# OR_Power_Switch.net
KiCad netlist of a schematic drawn in Altium Designer
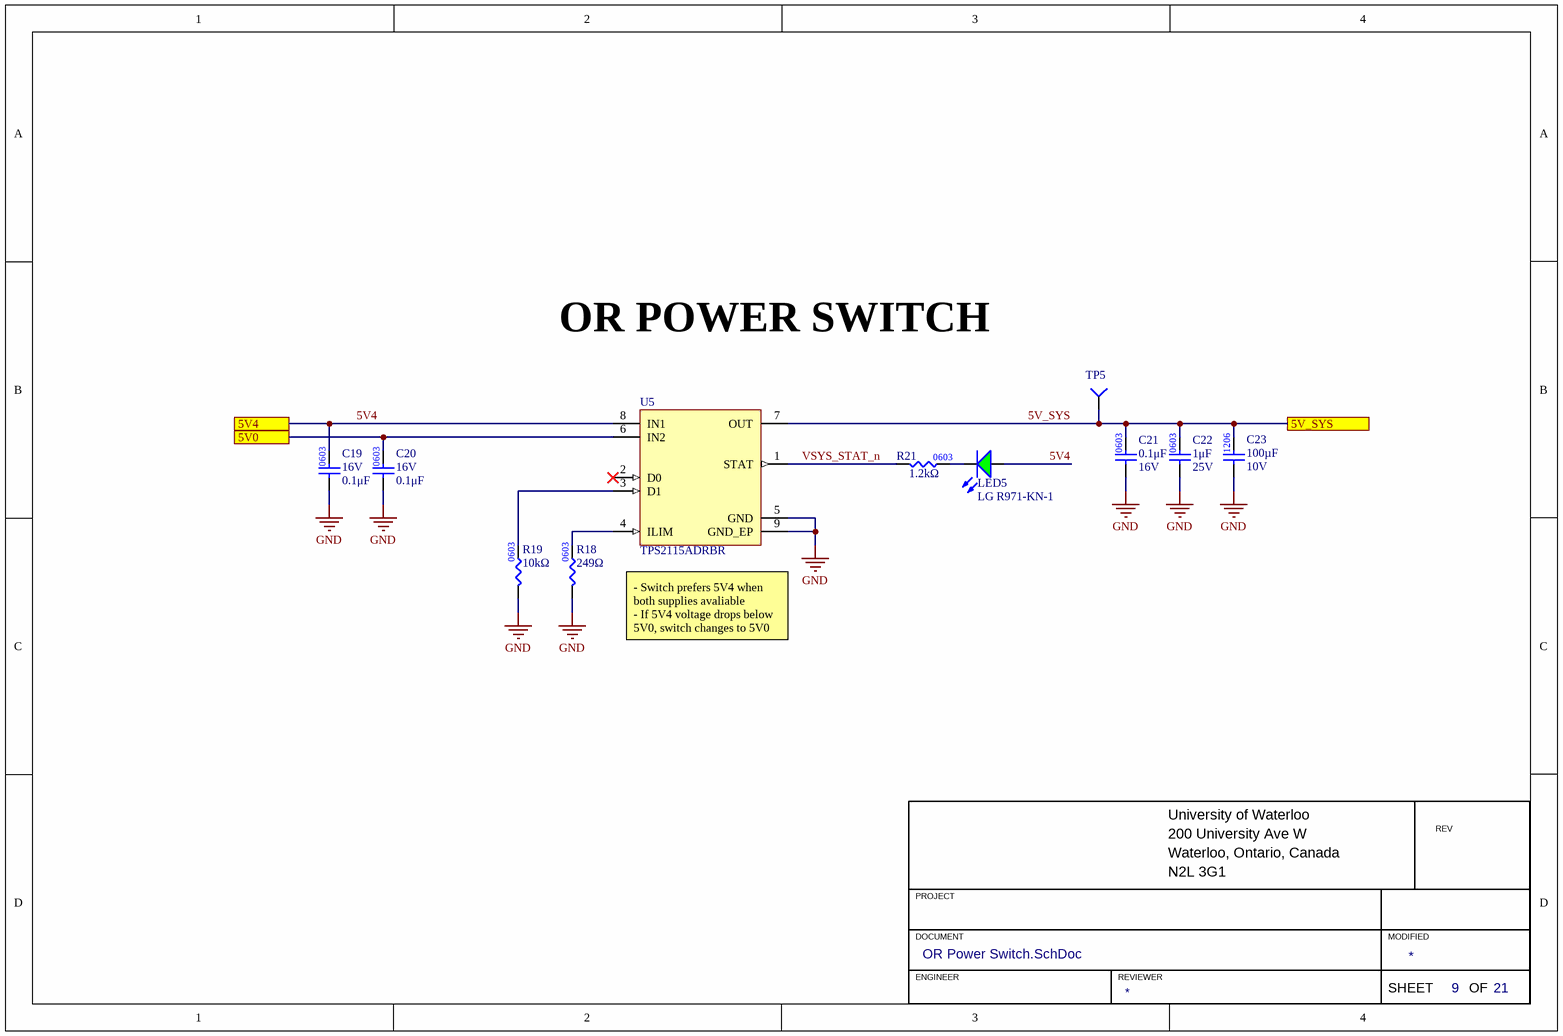
[diagram p0: OR Power Switch.SchDoc]

(export (version "E")
  (design (tool "Eeschema 10.0.6"))
  (components
    (comp (ref "C19")
      (value "0.1μF")
      (footprint "CAP0603")
      (description "CAP CER 0.1UF 16V X7R 0603")
      (fields (field (name "VOLTAGE RATING") "16V") (field (name "Comment") "CAP_0.1uF_16V_0603"))
      (libsource (lib "Personal_Schematic_Library_2022") (part "CAP_0.1uF_16V_0603"))
    )
    (comp (ref "C20")
      (value "0.1μF")
      (footprint "CAP0603")
      (description "CAP CER 0.1UF 16V X7R 0603")
      (fields (field (name "VOLTAGE RATING") "16V") (field (name "Comment") "CAP_0.1uF_16V_0603"))
      (libsource (lib "Personal_Schematic_Library_2022") (part "CAP_0.1uF_16V_0603"))
    )
    (comp (ref "C21")
      (value "0.1μF")
      (footprint "CAP0603")
      (description "CAP CER 0.1UF 16V X7R 0603")
      (fields (field (name "VOLTAGE RATING") "16V") (field (name "Comment") "CAP_0.1uF_16V_0603"))
      (libsource (lib "Personal_Schematic_Library_2022") (part "CAP_0.1uF_16V_0603"))
    )
    (comp (ref "C22")
      (value "1μF")
      (footprint "CAP0603")
      (description "CAP CER 1UF 25V X5R 0603")
      (fields (field (name "VOLTAGE RATING") "25V") (field (name "Comment") "CAP_1uF_25V_0603"))
      (libsource (lib "Personal_Schematic_Library_2022") (part "CAP_1uF_25V_0603"))
    )
    (comp (ref "C23")
      (value "100µF")
      (footprint "CAP1206")
      (description "CAP CER 100UF 10V X5R 1206")
      (fields (field (name "VOLTAGE RATING") "10V") (field (name "Comment") "CAP_100uF_10V_0603"))
      (libsource (lib "Personal_Schematic_Library_2022") (part "CAP_100uF_10V_0603"))
    )
    (comp (ref "LED5")
      (value "LED_GREEN_0805")
      (footprint "LED_0805_GREEN")
      (description "LED GREEN DIFFUSED 0805 SMD")
      (fields (field (name "MANUFACTURER PART NUMBER 1") "LG R971-KN-1"))
      (libsource (lib "Personal_Schematic_Library_2022") (part "LED_GREEN_0805"))
    )
    (comp (ref "R18")
      (value "249Ω")
      (footprint "RES0603")
      (description "RES 249 OHM 1% 1/10W 0603")
      (fields (field (name "Comment") "RES_249Ω_0603_1%"))
      (libsource (lib "Personal_Schematic_Library_2022") (part "RES_249Ω_0603_1%"))
    )
    (comp (ref "R19")
      (value "10kΩ")
      (footprint "RES0603")
      (description "RES 10K OHM 1% 1/8W 0603")
      (fields (field (name "Comment") "RES_10kΩ_0603_1%"))
      (libsource (lib "Personal_Schematic_Library_2022") (part "RES_10kΩ_0603_1%"))
    )
    (comp (ref "R21")
      (value "1.2kΩ")
      (footprint "RES0603")
      (description "RES 1.2K OHM 1% 1/10W 0603")
      (fields (field (name "Comment") "RES_1.2kΩ_0603_1%"))
      (libsource (lib "Personal_Schematic_Library_2022") (part "RES_1.2kΩ_0603_1%"))
    )
    (comp (ref "TP5")
      (value "TESTPOINT_KEYSTONE_LOOP")
      (footprint "KEYSTONE_5019")
      (description "PC TEST POINT MINIATURE")
      (libsource (lib "Personal_Schematic_Library_2022") (part "TESTPOINT_KEYSTONE_LOOP"))
    )
    (comp (ref "U5")
      (value "TPS2115ADRBR")
      (footprint "TI_8-VSON")
      (description "IC OR CTRLR SRC SELECT 8SON")
      (libsource (lib "Personal_Schematic_Library_2022") (part "TPS2115ADRBR"))
    )
  )
  (nets
    (net (code "1") (name "/5V0") (class "Default")
      (node (ref "C20") (pin "2") (pinfunction "2_2") (pintype "passive"))
      (node (ref "U5") (pin "6") (pinfunction "IN2_6") (pintype "power_in"))
    )
    (net (code "2") (name "/5V4") (class "Default")
      (node (ref "C19") (pin "2") (pinfunction "2_2") (pintype "passive"))
      (node (ref "LED5") (pin "1") (pinfunction "A_1") (pintype "passive"))
      (node (ref "U5") (pin "8") (pinfunction "IN1_8") (pintype "power_in"))
    )
    (net (code "3") (name "/5V_SYS") (class "Default")
      (node (ref "C21") (pin "2") (pinfunction "2_2") (pintype "passive"))
      (node (ref "C22") (pin "2") (pinfunction "2_2") (pintype "passive"))
      (node (ref "C23") (pin "2") (pinfunction "2_2") (pintype "passive"))
      (node (ref "TP5") (pin "1") (pinfunction "=value_1") (pintype "passive"))
      (node (ref "U5") (pin "7") (pinfunction "OUT_7") (pintype "power_in"))
    )
    (net (code "4") (name "/VSYS_STAT_n") (class "Default")
      (node (ref "R21") (pin "1") (pinfunction "1_1") (pintype "passive"))
      (node (ref "U5") (pin "1") (pinfunction "STAT_1") (pintype "output"))
    )
    (net (code "5") (name "GND") (class "Default")
      (node (ref "C19") (pin "1") (pinfunction "1_1") (pintype "passive"))
      (node (ref "C20") (pin "1") (pinfunction "1_1") (pintype "passive"))
      (node (ref "C21") (pin "1") (pinfunction "1_1") (pintype "passive"))
      (node (ref "C22") (pin "1") (pinfunction "1_1") (pintype "passive"))
      (node (ref "C23") (pin "1") (pinfunction "1_1") (pintype "passive"))
      (node (ref "R18") (pin "1") (pinfunction "1_1") (pintype "passive"))
      (node (ref "R19") (pin "1") (pinfunction "1_1") (pintype "passive"))
      (node (ref "U5") (pin "5") (pinfunction "GND_5") (pintype "power_in"))
      (node (ref "U5") (pin "9") (pinfunction "GND_EP_9") (pintype "power_in"))
    )
    (net (code "6") (name "Net-(LED5-K)") (class "Default")
      (node (ref "LED5") (pin "2") (pinfunction "K_2") (pintype "passive"))
      (node (ref "R21") (pin "2") (pinfunction "2_2") (pintype "passive"))
    )
    (net (code "7") (name "Net-(U5-D1)") (class "Default")
      (node (ref "R19") (pin "2") (pinfunction "2_2") (pintype "passive"))
      (node (ref "U5") (pin "3") (pinfunction "D1_3") (pintype "input"))
    )
    (net (code "8") (name "Net-(U5-ILIM)") (class "Default")
      (node (ref "R18") (pin "2") (pinfunction "2_2") (pintype "passive"))
      (node (ref "U5") (pin "4") (pinfunction "ILIM_4") (pintype "input"))
    )
    (net (code "9") (name "unconnected-(U5-D0-Pad2)") (class "Default")
      (node (ref "U5") (pin "2") (pinfunction "D0_2") (pintype "input+no_connect"))
    )
  )
)
